# Memory.net
KiCad netlist of a schematic drawn in Altium Designer
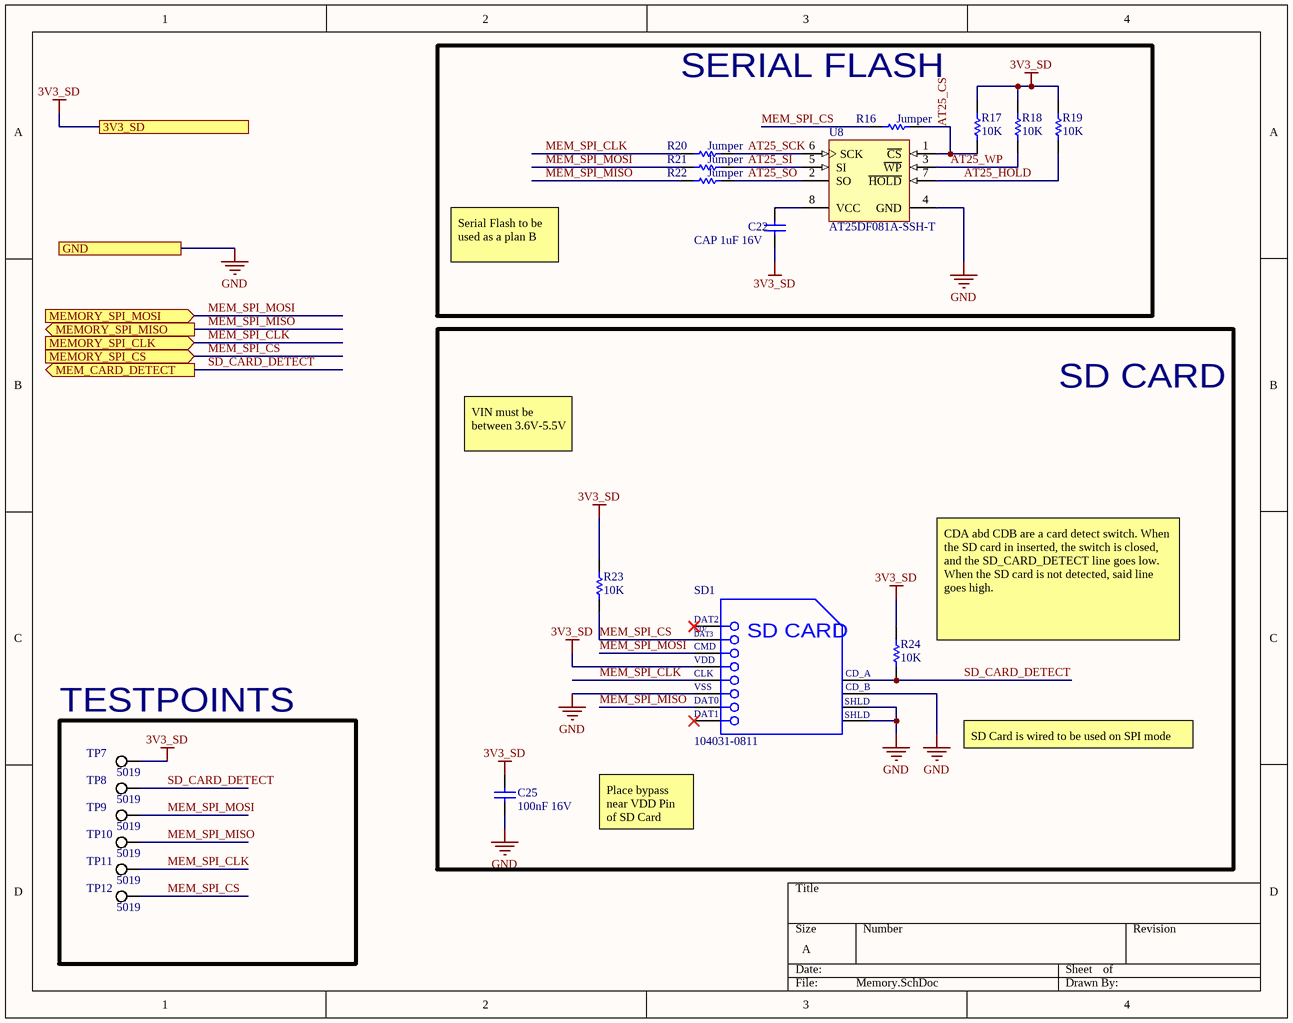
[diagram p0: Memory.SchDoc]

(export (version "E")
  (design (tool "Eeschema 10.0.6"))
  (components
    (comp (ref "C22")
      (value "CAP 1uF 16V")
      (footprint "CAPC0603(1608)100_N")
      (description "CAP 1uF 16V ±10% 0603 (1608 Metric) Thickness 1mm SMD")
      (fields (field (name "TOLERANCE") "Â±10%"))
      (libsource (lib "Altium Content Vault") (part "CAP"))
    )
    (comp (ref "C25")
      (value "100nF 16V")
      (footprint "CAPC0603(1608)100_N")
      (description "CAP 100nF 16V ±10% 0603 (1608 Metric) Thickness 1mm SMD")
      (fields (field (name "TOLERANCE") "Â±10%"))
      (libsource (lib "Altium Content Vault") (part "CAP"))
    )
    (comp (ref "R16")
      (value "Jumper")
      (footprint "RESC0603(1608)_N")
      (description "Jumper 0603 (1608 Metric)")
      (fields (field (name "POWER") "None"))
      (libsource (lib "Altium Content Vault") (part "RES"))
    )
    (comp (ref "R17")
      (value "10K")
      (footprint "RESC0402(1005)_M")
      (description "10K 0.063W 5% 0402 (1005 Metric)  SMD")
      (fields (field (name "TOLERANCE") "5 %") (field (name "POWER") "0.063 W"))
      (libsource (lib "Altium Content Vault") (part "CMP-1011-00098-1"))
    )
    (comp (ref "R18")
      (value "10K")
      (footprint "RESC0402(1005)_M")
      (description "10K 0.063W 5% 0402 (1005 Metric)  SMD")
      (fields (field (name "TOLERANCE") "5 %") (field (name "POWER") "0.063 W"))
      (libsource (lib "Altium Content Vault") (part "CMP-1011-00098-1"))
    )
    (comp (ref "R19")
      (value "10K")
      (footprint "RESC0402(1005)_M")
      (description "10K 0.063W 5% 0402 (1005 Metric)  SMD")
      (fields (field (name "TOLERANCE") "5 %") (field (name "POWER") "0.063 W"))
      (libsource (lib "Altium Content Vault") (part "CMP-1011-00098-1"))
    )
    (comp (ref "R20")
      (value "Jumper")
      (footprint "RESC0603(1608)_N")
      (description "Jumper 0603 (1608 Metric)")
      (fields (field (name "POWER") "None"))
      (libsource (lib "Altium Content Vault") (part "RES"))
    )
    (comp (ref "R21")
      (value "Jumper")
      (footprint "RESC0603(1608)_N")
      (description "Jumper 0603 (1608 Metric)")
      (fields (field (name "POWER") "None"))
      (libsource (lib "Altium Content Vault") (part "RES"))
    )
    (comp (ref "R22")
      (value "Jumper")
      (footprint "RESC0603(1608)_N")
      (description "Jumper 0603 (1608 Metric)")
      (fields (field (name "POWER") "None"))
      (libsource (lib "Altium Content Vault") (part "RES"))
    )
    (comp (ref "R23")
      (value "10K")
      (footprint "RESC0402(1005)_M")
      (description "10K 0.063W 5% 0402 (1005 Metric)  SMD")
      (fields (field (name "TOLERANCE") "5 %") (field (name "POWER") "0.063 W"))
      (libsource (lib "Altium Content Vault") (part "CMP-1011-00098-1"))
    )
    (comp (ref "R24")
      (value "10K")
      (footprint "RESC0402(1005)_M")
      (description "10K 0.063W 5% 0402 (1005 Metric)  SMD")
      (fields (field (name "TOLERANCE") "5 %") (field (name "POWER") "0.063 W"))
      (libsource (lib "Altium Content Vault") (part "CMP-1011-00098-1"))
    )
    (comp (ref "SD1")
      (value "104031-0811")
      (footprint "MOLX-104031-0811_V")
      (description "Micro SD Card, RA, -25 to 85 degC, 8-Pin SMD, RoHS, Tape and Reel")
      (fields (field (name "MANUFACTURER") "Molex"))
      (libsource (lib "Altium Content Vault") (part "CN-SD-8-2SW-2S"))
    )
    (comp (ref "TP7")
      (value "5019")
      (footprint "KSTN-5019_V")
      (description "Test Point, 1 Position SMD, RoHS, Tape and Reel")
      (libsource (lib "Altium Content Vault") (part "TESTPOINT_WHITE"))
    )
    (comp (ref "TP8")
      (value "5019")
      (footprint "KSTN-5019_V")
      (description "Test Point, 1 Position SMD, RoHS, Tape and Reel")
      (libsource (lib "Altium Content Vault") (part "TESTPOINT_WHITE"))
    )
    (comp (ref "TP9")
      (value "5019")
      (footprint "KSTN-5019_V")
      (description "Test Point, 1 Position SMD, RoHS, Tape and Reel")
      (libsource (lib "Altium Content Vault") (part "TESTPOINT_WHITE"))
    )
    (comp (ref "TP10")
      (value "5019")
      (footprint "KSTN-5019_V")
      (description "Test Point, 1 Position SMD, RoHS, Tape and Reel")
      (libsource (lib "Altium Content Vault") (part "TESTPOINT_WHITE"))
    )
    (comp (ref "TP11")
      (value "5019")
      (footprint "KSTN-5019_V")
      (description "Test Point, 1 Position SMD, RoHS, Tape and Reel")
      (libsource (lib "Altium Content Vault") (part "TESTPOINT_WHITE"))
    )
    (comp (ref "TP12")
      (value "5019")
      (footprint "KSTN-5019_V")
      (description "Test Point, 1 Position SMD, RoHS, Tape and Reel")
      (libsource (lib "Altium Content Vault") (part "TESTPOINT_WHITE"))
    )
    (comp (ref "U8")
      (value "AT25DF081A-SSH-T")
      (footprint "AT25DF081A-SSH-T")
      (description "IC FLASH 8MBIT 100MHZ 8SOIC")
      (fields (field (name "MANUFACTURER") "Adesto Technologies"))
      (libsource (lib "Schematics") (part "AT25DF081A-SSH-T"))
    )
  )
  (nets
    (net (code "1") (name "/AT25_CS") (class "Default")
      (node (ref "R16") (pin "2") (pinfunction "2_2") (pintype "passive"))
      (node (ref "R17") (pin "2") (pinfunction "2_2") (pintype "passive"))
      (node (ref "U8") (pin "1") (pinfunction "~{CS}_1") (pintype "input"))
    )
    (net (code "2") (name "/AT25_HOLD") (class "Default")
      (node (ref "R19") (pin "2") (pinfunction "2_2") (pintype "passive"))
      (node (ref "U8") (pin "7") (pinfunction "~{HOLD}_7") (pintype "input"))
    )
    (net (code "3") (name "/AT25_SCK") (class "Default")
      (node (ref "R20") (pin "2") (pinfunction "2_2") (pintype "passive"))
      (node (ref "U8") (pin "6") (pinfunction "SCK_6") (pintype "input"))
    )
    (net (code "4") (name "/AT25_SI") (class "Default")
      (node (ref "R21") (pin "2") (pinfunction "2_2") (pintype "passive"))
      (node (ref "U8") (pin "5") (pinfunction "SI_5") (pintype "input"))
    )
    (net (code "5") (name "/AT25_SO") (class "Default")
      (node (ref "R22") (pin "2") (pinfunction "2_2") (pintype "passive"))
      (node (ref "U8") (pin "2") (pinfunction "SO_2") (pintype "tri_state"))
    )
    (net (code "6") (name "/AT25_WP") (class "Default")
      (node (ref "R18") (pin "2") (pinfunction "2_2") (pintype "passive"))
      (node (ref "U8") (pin "3") (pinfunction "~{WP}_3") (pintype "input"))
    )
    (net (code "7") (name "/MEM_SPI_CLK") (class "Default")
      (node (ref "R20") (pin "1") (pinfunction "1_1") (pintype "passive"))
      (node (ref "SD1") (pin "5") (pinfunction "CLK_5") (pintype "passive"))
      (node (ref "TP11") (pin "1") (pinfunction "1_1") (pintype "passive"))
    )
    (net (code "8") (name "/MEM_SPI_CS") (class "Default")
      (node (ref "R16") (pin "1") (pinfunction "1_1") (pintype "passive"))
      (node (ref "R23") (pin "2") (pinfunction "2_2") (pintype "passive"))
      (node (ref "SD1") (pin "2") (pinfunction "CMD_2") (pintype "passive"))
      (node (ref "TP12") (pin "1") (pinfunction "1_1") (pintype "passive"))
    )
    (net (code "9") (name "/MEM_SPI_MISO") (class "Default")
      (node (ref "R22") (pin "1") (pinfunction "1_1") (pintype "passive"))
      (node (ref "SD1") (pin "7") (pinfunction "DAT0_7") (pintype "passive"))
      (node (ref "TP10") (pin "1") (pinfunction "1_1") (pintype "passive"))
    )
    (net (code "10") (name "/MEM_SPI_MOSI") (class "Default")
      (node (ref "R21") (pin "1") (pinfunction "1_1") (pintype "passive"))
      (node (ref "SD1") (pin "3") (pinfunction "VSS1_3") (pintype "passive"))
      (node (ref "TP9") (pin "1") (pinfunction "1_1") (pintype "passive"))
    )
    (net (code "11") (name "/SD_CARD_DETECT") (class "Default")
      (node (ref "R24") (pin "2") (pinfunction "2_2") (pintype "passive"))
      (node (ref "SD1") (pin "9") (pinfunction "CD_A_9") (pintype "passive"))
      (node (ref "TP8") (pin "1") (pinfunction "1_1") (pintype "passive"))
    )
    (net (code "12") (name "3V3_SD") (class "Default")
      (node (ref "C22") (pin "1") (pinfunction "1_1") (pintype "passive"))
      (node (ref "C25") (pin "2") (pinfunction "2_2") (pintype "passive"))
      (node (ref "R17") (pin "1") (pinfunction "1_1") (pintype "passive"))
      (node (ref "R18") (pin "1") (pinfunction "1_1") (pintype "passive"))
      (node (ref "R19") (pin "1") (pinfunction "1_1") (pintype "passive"))
      (node (ref "R23") (pin "1") (pinfunction "1_1") (pintype "passive"))
      (node (ref "R24") (pin "1") (pinfunction "1_1") (pintype "passive"))
      (node (ref "SD1") (pin "4") (pinfunction "VDD_4") (pintype "passive"))
      (node (ref "TP7") (pin "1") (pinfunction "1_1") (pintype "passive"))
    )
    (net (code "13") (name "GND") (class "Default")
      (node (ref "C25") (pin "1") (pinfunction "1_1") (pintype "passive"))
      (node (ref "SD1") (pin "10") (pinfunction "CD_B_10") (pintype "passive"))
      (node (ref "SD1") (pin "11") (pinfunction "SHLD1_11") (pintype "passive"))
      (node (ref "SD1") (pin "12") (pinfunction "SHLD2_12") (pintype "passive"))
      (node (ref "SD1") (pin "6") (pinfunction "VSS2_6") (pintype "passive"))
      (node (ref "U8") (pin "4") (pinfunction "GND_4") (pintype "power_in"))
    )
    (net (code "14") (name "Net-(U8-VCC)") (class "Default")
      (node (ref "C22") (pin "2") (pinfunction "2_2") (pintype "passive"))
      (node (ref "U8") (pin "8") (pinfunction "VCC_8") (pintype "power_in"))
    )
    (net (code "15") (name "unconnected-(SD1-CD{slash}DAT3-Pad1)") (class "Default")
      (node (ref "SD1") (pin "1") (pinfunction "CD/DAT3_1") (pintype "passive+no_connect"))
    )
    (net (code "16") (name "unconnected-(SD1-DAT1-Pad8)") (class "Default")
      (node (ref "SD1") (pin "8") (pinfunction "DAT1_8") (pintype "passive+no_connect"))
    )
  )
)
